# FETishOnAStick.net
KiCad netlist of a schematic drawn in EAGLE
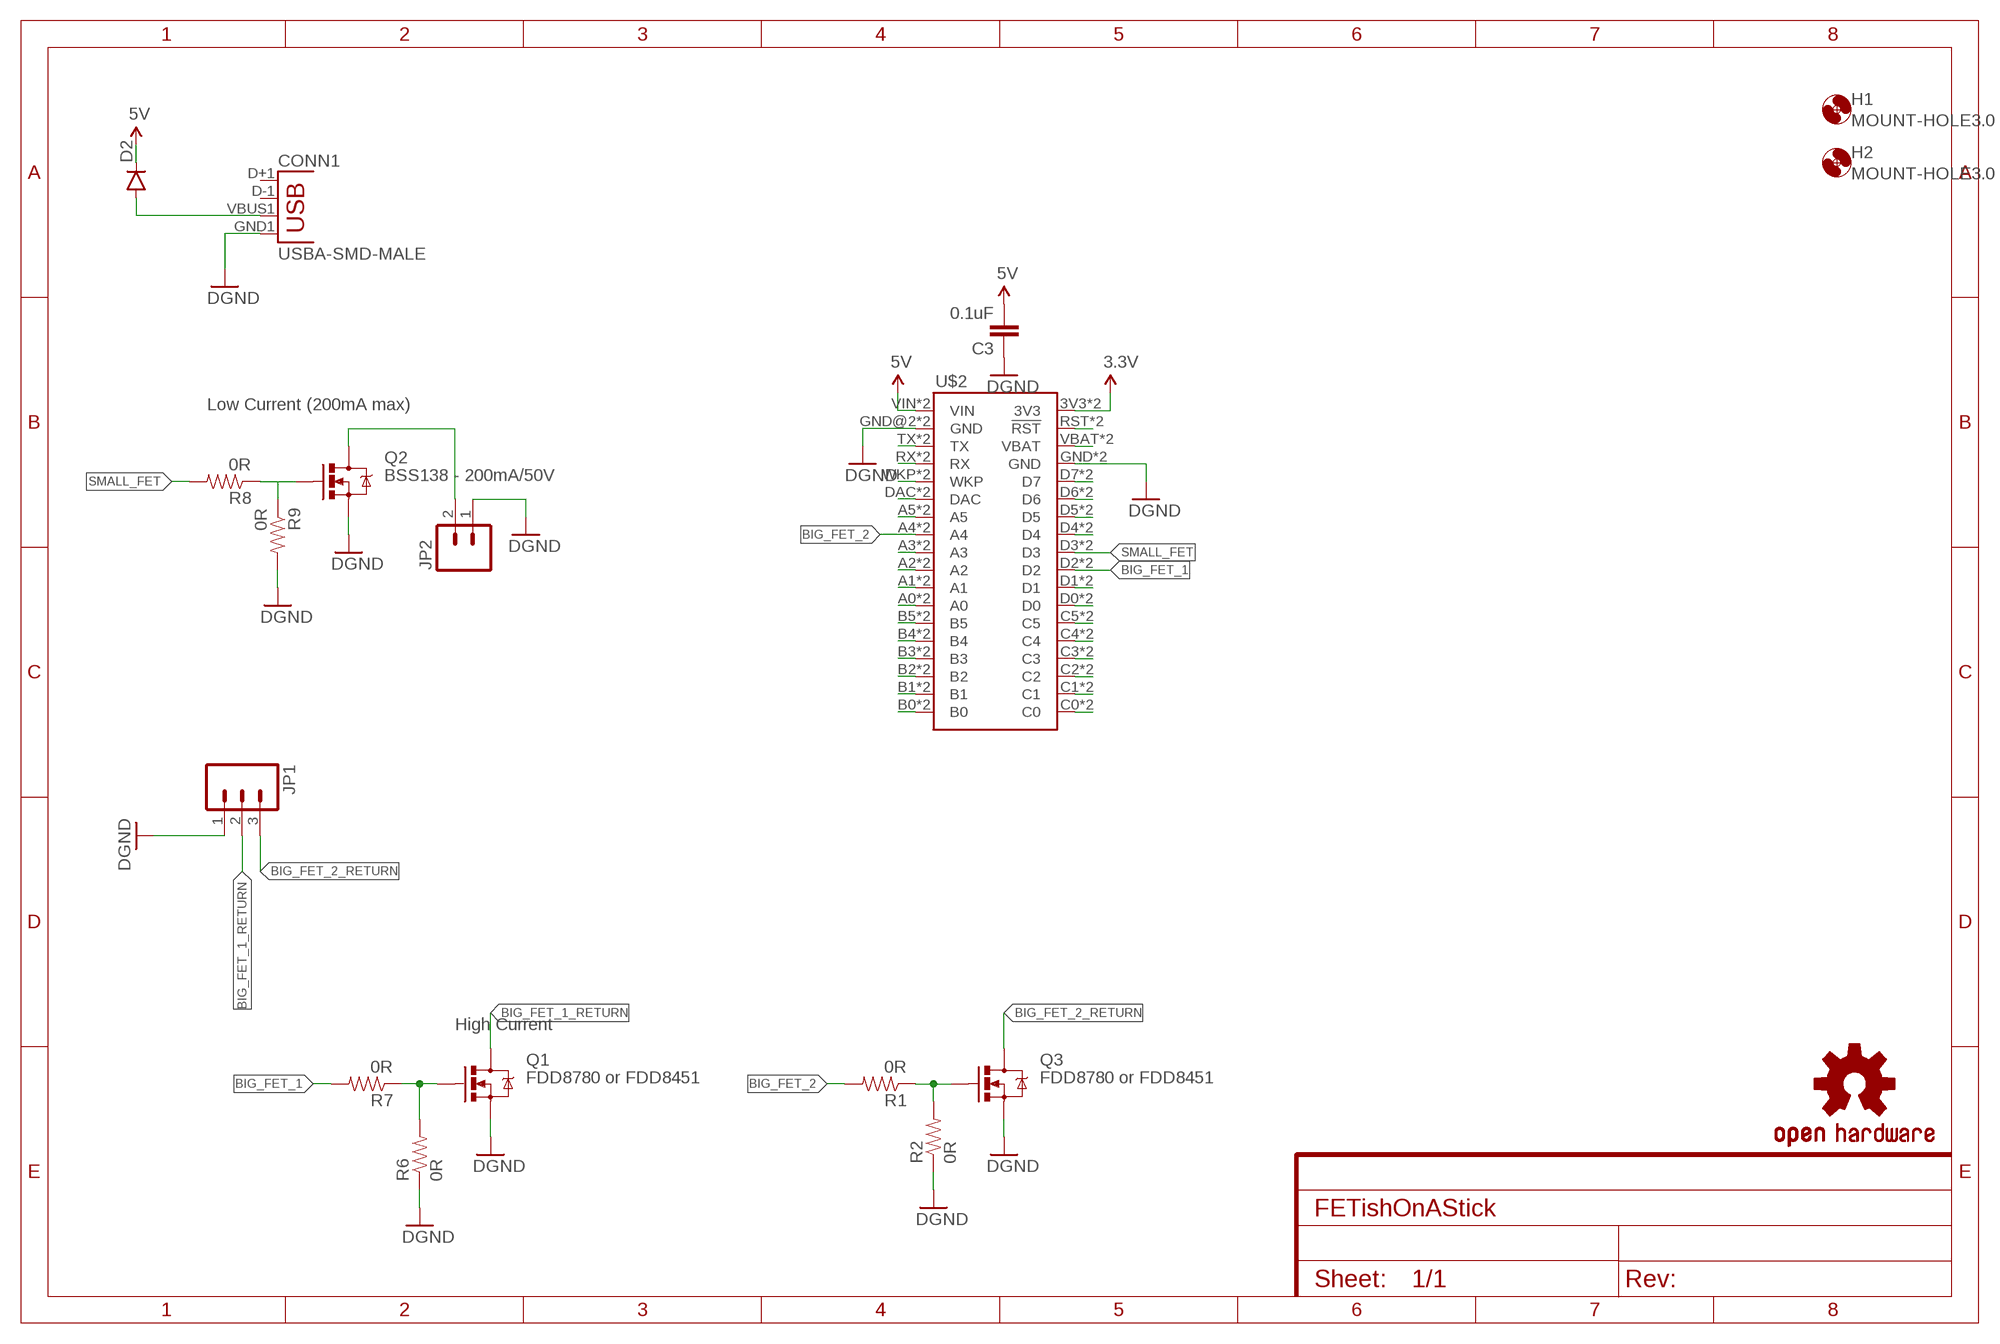
[diagram p0: schematic, sheet 1]

(export (version "E")
  (design (tool "Eeschema 10.0.6"))
  (components
    (comp (ref "C3")
      (value "0.1uF")
      (footprint "eagle-import:0805")
      (libsource (lib "eagle-import") (part "CAP0805"))
    )
    (comp (ref "CONN1")
      (value "USBA-SMD-MALE")
      (footprint "eagle-import:USB-A-SMT-MALE")
      (libsource (lib "eagle-import") (part "USBA-SMD-MALE"))
    )
    (comp (ref "D2")
      (value "DIODESMA")
      (footprint "eagle-import:SMA-DIODE")
      (libsource (lib "eagle-import") (part "DIODESMA"))
    )
    (comp (ref "H1")
      (value "MOUNT-HOLE3.0")
      (footprint "eagle-import:3,0")
      (libsource (lib "eagle-import") (part "MOUNT-HOLE3.0"))
    )
    (comp (ref "H2")
      (value "MOUNT-HOLE3.0")
      (footprint "eagle-import:3,0")
      (libsource (lib "eagle-import") (part "MOUNT-HOLE3.0"))
    )
    (comp (ref "JP1")
      (value "M03-SCREW-5MM")
      (footprint "eagle-import:SCREWTERMINAL-5MM-3")
      (libsource (lib "eagle-import") (part "M03-SCREW-5MM"))
    )
    (comp (ref "JP2")
      (value "M02POLAR")
      (footprint "eagle-import:MOLEX-1X2")
      (libsource (lib "eagle-import") (part "M02POLAR"))
    )
    (comp (ref "LOGO2")
      (value "OSHW-LOGOS")
      (footprint "eagle-import:OSHW-LOGO-S")
      (libsource (lib "eagle-import") (part "OSHW-LOGOS"))
    )
    (comp (ref "Q1")
      (value "FDD8780 or FDD8451")
      (footprint "eagle-import:DPAK")
      (libsource (lib "eagle-import") (part "MOSFET-NCHANNELFDD8780"))
    )
    (comp (ref "Q2")
      (value "BSS138 - 200mA/50V")
      (footprint "eagle-import:SOT23-3")
      (libsource (lib "eagle-import") (part "MOSFET-NCHANNELBSS138"))
    )
    (comp (ref "Q3")
      (value "FDD8780 or FDD8451")
      (footprint "eagle-import:DPAK")
      (libsource (lib "eagle-import") (part "MOSFET-NCHANNELFDD8780"))
    )
    (comp (ref "R1")
      (value "0R")
      (footprint "eagle-import:0805")
      (libsource (lib "eagle-import") (part "RESISTOR0805-RES"))
    )
    (comp (ref "R2")
      (value "0R")
      (footprint "eagle-import:0805")
      (libsource (lib "eagle-import") (part "RESISTOR0805-RES"))
    )
    (comp (ref "R6")
      (value "0R")
      (footprint "eagle-import:0805")
      (libsource (lib "eagle-import") (part "RESISTOR0805-RES"))
    )
    (comp (ref "R7")
      (value "0R")
      (footprint "eagle-import:0805")
      (libsource (lib "eagle-import") (part "RESISTOR0805-RES"))
    )
    (comp (ref "R8")
      (value "0R")
      (footprint "eagle-import:0805")
      (libsource (lib "eagle-import") (part "RESISTOR0805-RES"))
    )
    (comp (ref "R9")
      (value "0R")
      (footprint "eagle-import:0805")
      (libsource (lib "eagle-import") (part "RESISTOR0805-RES"))
    )
    (comp (ref "U$2")
      (value "ELECTRONDUALNAMED")
      (footprint "eagle-import:ELECTRON_SIMPLE_SILK_NAMES_DUAL")
      (libsource (lib "eagle-import") (part "ELECTRONDUALNAMED"))
    )
  )
  (nets
    (net (code "1") (name "3.3V") (class "Default")
      (node (ref "U$2") (pin "3V3") (pinfunction "3V3_3V3") (pintype "power_in"))
      (node (ref "U$2") (pin "3V3_1") (pinfunction "3V3_3V3_1") (pintype "power_in"))
    )
    (net (code "2") (name "5V") (class "Default")
      (node (ref "C3") (pin "2") (pinfunction "2_2") (pintype "passive"))
      (node (ref "D2") (pin "C") (pinfunction "C_C") (pintype "passive"))
      (node (ref "U$2") (pin "VIN") (pinfunction "VIN_VIN") (pintype "power_in"))
      (node (ref "U$2") (pin "VIN_1B") (pinfunction "VIN_VIN_1B") (pintype "power_in"))
    )
    (net (code "3") (name "BIG_FET_1") (class "Default")
      (node (ref "R7") (pin "2") (pinfunction "2_2") (pintype "passive"))
      (node (ref "U$2") (pin "D2") (pinfunction "D2_D2") (pintype "bidirectional"))
      (node (ref "U$2") (pin "D2_1") (pinfunction "D2_D2_1") (pintype "bidirectional"))
    )
    (net (code "4") (name "BIG_FET_1_RETURN") (class "Default")
      (node (ref "JP1") (pin "2") (pinfunction "2_2") (pintype "passive"))
      (node (ref "Q1") (pin "4") (pinfunction "D_4") (pintype "passive"))
    )
    (net (code "5") (name "BIG_FET_2") (class "Default")
      (node (ref "R1") (pin "2") (pinfunction "2_2") (pintype "passive"))
      (node (ref "U$2") (pin "A4") (pinfunction "A4_A4") (pintype "bidirectional"))
      (node (ref "U$2") (pin "A4_1") (pinfunction "A4_A4_1") (pintype "bidirectional"))
    )
    (net (code "6") (name "BIG_FET_2_RETURN") (class "Default")
      (node (ref "JP1") (pin "3") (pinfunction "3_3") (pintype "passive"))
      (node (ref "Q3") (pin "4") (pinfunction "D_4") (pintype "passive"))
    )
    (net (code "7") (name "DGND") (class "Default")
      (node (ref "C3") (pin "1") (pinfunction "1_1") (pintype "passive"))
      (node (ref "CONN1") (pin "GND1") (pinfunction "GND_GND1") (pintype "bidirectional"))
      (node (ref "JP1") (pin "1") (pinfunction "1_1") (pintype "passive"))
      (node (ref "JP2") (pin "1") (pinfunction "1_1") (pintype "passive"))
      (node (ref "Q1") (pin "3") (pinfunction "S_3") (pintype "passive"))
      (node (ref "Q2") (pin "2") (pinfunction "S_2") (pintype "passive"))
      (node (ref "Q3") (pin "3") (pinfunction "S_3") (pintype "passive"))
      (node (ref "R2") (pin "1") (pinfunction "1_1") (pintype "passive"))
      (node (ref "R6") (pin "1") (pinfunction "1_1") (pintype "passive"))
      (node (ref "R9") (pin "2") (pinfunction "2_2") (pintype "passive"))
      (node (ref "U$2") (pin "GND") (pinfunction "GND_GND") (pintype "power_in"))
      (node (ref "U$2") (pin "GND@2") (pinfunction "GND_GND@2") (pintype "power_in"))
      (node (ref "U$2") (pin "GND_1") (pinfunction "GND_GND_1") (pintype "power_in"))
      (node (ref "U$2") (pin "GND_1B") (pinfunction "GND_GND_1B") (pintype "power_in"))
    )
    (net (code "8") (name "Net-(CONN1-VBUS)") (class "Default")
      (node (ref "CONN1") (pin "VBUS1") (pinfunction "VBUS_VBUS1") (pintype "bidirectional"))
      (node (ref "D2") (pin "A") (pinfunction "A_A") (pintype "passive"))
    )
    (net (code "9") (name "Net-(Q1-G)") (class "Default")
      (node (ref "Q1") (pin "1") (pinfunction "G_1") (pintype "passive"))
      (node (ref "R6") (pin "2") (pinfunction "2_2") (pintype "passive"))
      (node (ref "R7") (pin "1") (pinfunction "1_1") (pintype "passive"))
    )
    (net (code "10") (name "Net-(Q2-D)") (class "Default")
      (node (ref "JP2") (pin "2") (pinfunction "2_2") (pintype "passive"))
      (node (ref "Q2") (pin "3") (pinfunction "D_3") (pintype "passive"))
    )
    (net (code "11") (name "Net-(Q2-G)") (class "Default")
      (node (ref "Q2") (pin "1") (pinfunction "G_1") (pintype "passive"))
      (node (ref "R8") (pin "1") (pinfunction "1_1") (pintype "passive"))
      (node (ref "R9") (pin "1") (pinfunction "1_1") (pintype "passive"))
    )
    (net (code "12") (name "Net-(Q3-G)") (class "Default")
      (node (ref "Q3") (pin "1") (pinfunction "G_1") (pintype "passive"))
      (node (ref "R1") (pin "1") (pinfunction "1_1") (pintype "passive"))
      (node (ref "R2") (pin "2") (pinfunction "2_2") (pintype "passive"))
    )
    (net (code "13") (name "Net-(U$2-A0-PadA0_1)") (class "Default")
      (node (ref "U$2") (pin "A0") (pinfunction "A0_A0") (pintype "bidirectional"))
      (node (ref "U$2") (pin "A0_1") (pinfunction "A0_A0_1") (pintype "bidirectional"))
    )
    (net (code "14") (name "Net-(U$2-A1-PadA1_1)") (class "Default")
      (node (ref "U$2") (pin "A1") (pinfunction "A1_A1") (pintype "bidirectional"))
      (node (ref "U$2") (pin "A1_1") (pinfunction "A1_A1_1") (pintype "bidirectional"))
    )
    (net (code "15") (name "Net-(U$2-A2-PadA2_1)") (class "Default")
      (node (ref "U$2") (pin "A2") (pinfunction "A2_A2") (pintype "bidirectional"))
      (node (ref "U$2") (pin "A2_1") (pinfunction "A2_A2_1") (pintype "bidirectional"))
    )
    (net (code "16") (name "Net-(U$2-A3-PadA3_1)") (class "Default")
      (node (ref "U$2") (pin "A3") (pinfunction "A3_A3") (pintype "bidirectional"))
      (node (ref "U$2") (pin "A3_1") (pinfunction "A3_A3_1") (pintype "bidirectional"))
    )
    (net (code "17") (name "Net-(U$2-A5-PadA5_1)") (class "Default")
      (node (ref "U$2") (pin "A5") (pinfunction "A5_A5") (pintype "bidirectional"))
      (node (ref "U$2") (pin "A5_1") (pinfunction "A5_A5_1") (pintype "bidirectional"))
    )
    (net (code "18") (name "Net-(U$2-B0-PadB0_1)") (class "Default")
      (node (ref "U$2") (pin "B0") (pinfunction "B0_B0") (pintype "bidirectional"))
      (node (ref "U$2") (pin "B0_1") (pinfunction "B0_B0_1") (pintype "bidirectional"))
    )
    (net (code "19") (name "Net-(U$2-B1-PadB1_1)") (class "Default")
      (node (ref "U$2") (pin "B1") (pinfunction "B1_B1") (pintype "bidirectional"))
      (node (ref "U$2") (pin "B1_1") (pinfunction "B1_B1_1") (pintype "bidirectional"))
    )
    (net (code "20") (name "Net-(U$2-B2-PadB2_1)") (class "Default")
      (node (ref "U$2") (pin "B2") (pinfunction "B2_B2") (pintype "bidirectional"))
      (node (ref "U$2") (pin "B2_1") (pinfunction "B2_B2_1") (pintype "bidirectional"))
    )
    (net (code "21") (name "Net-(U$2-B3-PadB3_1)") (class "Default")
      (node (ref "U$2") (pin "B3") (pinfunction "B3_B3") (pintype "bidirectional"))
      (node (ref "U$2") (pin "B3_1") (pinfunction "B3_B3_1") (pintype "bidirectional"))
    )
    (net (code "22") (name "Net-(U$2-B4-PadB4_1)") (class "Default")
      (node (ref "U$2") (pin "B4") (pinfunction "B4_B4") (pintype "bidirectional"))
      (node (ref "U$2") (pin "B4_1") (pinfunction "B4_B4_1") (pintype "bidirectional"))
    )
    (net (code "23") (name "Net-(U$2-B5-PadB5_1)") (class "Default")
      (node (ref "U$2") (pin "B5") (pinfunction "B5_B5") (pintype "bidirectional"))
      (node (ref "U$2") (pin "B5_1") (pinfunction "B5_B5_1") (pintype "bidirectional"))
    )
    (net (code "24") (name "Net-(U$2-C0-PadC0_1)") (class "Default")
      (node (ref "U$2") (pin "C0") (pinfunction "C0_C0") (pintype "bidirectional"))
      (node (ref "U$2") (pin "C0_1") (pinfunction "C0_C0_1") (pintype "bidirectional"))
    )
    (net (code "25") (name "Net-(U$2-C1-PadC1_1)") (class "Default")
      (node (ref "U$2") (pin "C1") (pinfunction "C1_C1") (pintype "bidirectional"))
      (node (ref "U$2") (pin "C1_1") (pinfunction "C1_C1_1") (pintype "bidirectional"))
    )
    (net (code "26") (name "Net-(U$2-C2-PadC2_1)") (class "Default")
      (node (ref "U$2") (pin "C2") (pinfunction "C2_C2") (pintype "bidirectional"))
      (node (ref "U$2") (pin "C2_1") (pinfunction "C2_C2_1") (pintype "bidirectional"))
    )
    (net (code "27") (name "Net-(U$2-C3-PadC3_1)") (class "Default")
      (node (ref "U$2") (pin "C3") (pinfunction "C3_C3") (pintype "bidirectional"))
      (node (ref "U$2") (pin "C3_1") (pinfunction "C3_C3_1") (pintype "bidirectional"))
    )
    (net (code "28") (name "Net-(U$2-C4-PadC4_1)") (class "Default")
      (node (ref "U$2") (pin "C4") (pinfunction "C4_C4") (pintype "bidirectional"))
      (node (ref "U$2") (pin "C4_1") (pinfunction "C4_C4_1") (pintype "bidirectional"))
    )
    (net (code "29") (name "Net-(U$2-C5-PadC5_1)") (class "Default")
      (node (ref "U$2") (pin "C5") (pinfunction "C5_C5") (pintype "bidirectional"))
      (node (ref "U$2") (pin "C5_1") (pinfunction "C5_C5_1") (pintype "bidirectional"))
    )
    (net (code "30") (name "Net-(U$2-D0-PadD0_1)") (class "Default")
      (node (ref "U$2") (pin "D0") (pinfunction "D0_D0") (pintype "bidirectional"))
      (node (ref "U$2") (pin "D0_1") (pinfunction "D0_D0_1") (pintype "bidirectional"))
    )
    (net (code "31") (name "Net-(U$2-D1-PadD1_1)") (class "Default")
      (node (ref "U$2") (pin "D1") (pinfunction "D1_D1") (pintype "bidirectional"))
      (node (ref "U$2") (pin "D1_1") (pinfunction "D1_D1_1") (pintype "bidirectional"))
    )
    (net (code "32") (name "Net-(U$2-D4-PadD4_1)") (class "Default")
      (node (ref "U$2") (pin "D4") (pinfunction "D4_D4") (pintype "bidirectional"))
      (node (ref "U$2") (pin "D4_1") (pinfunction "D4_D4_1") (pintype "bidirectional"))
    )
    (net (code "33") (name "Net-(U$2-D5-PadD5_1)") (class "Default")
      (node (ref "U$2") (pin "D5") (pinfunction "D5_D5") (pintype "bidirectional"))
      (node (ref "U$2") (pin "D5_1") (pinfunction "D5_D5_1") (pintype "bidirectional"))
    )
    (net (code "34") (name "Net-(U$2-D6-PadD6_1)") (class "Default")
      (node (ref "U$2") (pin "D6") (pinfunction "D6_D6") (pintype "bidirectional"))
      (node (ref "U$2") (pin "D6_1") (pinfunction "D6_D6_1") (pintype "bidirectional"))
    )
    (net (code "35") (name "Net-(U$2-D7-PadD7_1)") (class "Default")
      (node (ref "U$2") (pin "D7") (pinfunction "D7_D7") (pintype "bidirectional"))
      (node (ref "U$2") (pin "D7_1") (pinfunction "D7_D7_1") (pintype "bidirectional"))
    )
    (net (code "36") (name "Net-(U$2-DAC-PadDAC_1)") (class "Default")
      (node (ref "U$2") (pin "DAC") (pinfunction "DAC_DAC") (pintype "bidirectional"))
      (node (ref "U$2") (pin "DAC_1") (pinfunction "DAC_DAC_1") (pintype "bidirectional"))
    )
    (net (code "37") (name "Net-(U$2-PadRX)") (class "Default")
      (node (ref "U$2") (pin "RX") (pinfunction "RX_RX") (pintype "bidirectional"))
      (node (ref "U$2") (pin "RX_1") (pinfunction "RX_RX_1") (pintype "bidirectional"))
    )
    (net (code "38") (name "Net-(U$2-PadTX)") (class "Default")
      (node (ref "U$2") (pin "TX") (pinfunction "TX_TX") (pintype "bidirectional"))
      (node (ref "U$2") (pin "TX_1") (pinfunction "TX_TX_1") (pintype "bidirectional"))
    )
    (net (code "39") (name "Net-(U$2-PadVBAT)") (class "Default")
      (node (ref "U$2") (pin "VBAT") (pinfunction "VBAT_VBAT") (pintype "passive"))
      (node (ref "U$2") (pin "VBATT_1") (pinfunction "VBAT_VBATT_1") (pintype "passive"))
    )
    (net (code "40") (name "Net-(U$2-PadWKP)") (class "Default")
      (node (ref "U$2") (pin "WKP") (pinfunction "WKP_WKP") (pintype "bidirectional"))
      (node (ref "U$2") (pin "WKP_1") (pinfunction "WKP_WKP_1") (pintype "bidirectional"))
    )
    (net (code "41") (name "Net-(U$2-~{RST}-PadRST)") (class "Default")
      (node (ref "U$2") (pin "RST") (pinfunction "~{RST}_RST") (pintype "bidirectional"))
      (node (ref "U$2") (pin "RST_1") (pinfunction "~{RST}_RST_1") (pintype "bidirectional"))
    )
    (net (code "42") (name "SMALL_FET") (class "Default")
      (node (ref "R8") (pin "2") (pinfunction "2_2") (pintype "passive"))
      (node (ref "U$2") (pin "D3") (pinfunction "D3_D3") (pintype "bidirectional"))
      (node (ref "U$2") (pin "D3_1") (pinfunction "D3_D3_1") (pintype "bidirectional"))
    )
    (net (code "43") (name "unconnected-(CONN1-D+-PadD+1)") (class "Default")
      (node (ref "CONN1") (pin "D+1") (pinfunction "D+_D+1") (pintype "bidirectional"))
    )
    (net (code "44") (name "unconnected-(CONN1-D--PadD-1)") (class "Default")
      (node (ref "CONN1") (pin "D-1") (pinfunction "D-_D-1") (pintype "bidirectional"))
    )
  )
)
